# TLC5973.net
KiCad netlist of a schematic drawn in EAGLE
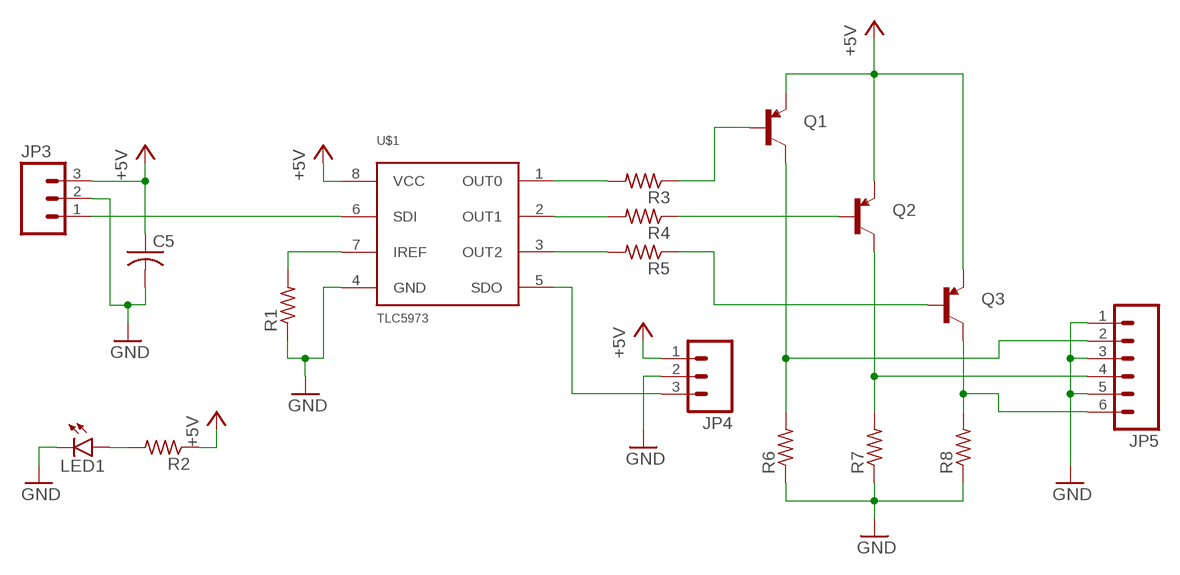
[diagram p0: schematic, sheet 1]

(export (version "E")
  (design (tool "Eeschema 10.0.6"))
  (components
    (comp (ref "C5")
      (value "C-USC0805K")
      (footprint "eagle-import:C0805K")
      (libsource (lib "eagle-import") (part "C-USC0805K"))
    )
    (comp (ref "JP3")
      (value "M03LOCK")
      (footprint "eagle-import:1X03_LOCK")
      (libsource (lib "eagle-import") (part "M03LOCK"))
    )
    (comp (ref "JP4")
      (value "M03LOCK")
      (footprint "eagle-import:1X03_LOCK")
      (libsource (lib "eagle-import") (part "M03LOCK"))
    )
    (comp (ref "JP5")
      (value "M06LOCK")
      (footprint "eagle-import:1X06_LOCK")
      (libsource (lib "eagle-import") (part "M06LOCK"))
    )
    (comp (ref "LED1")
      (value "LED1206")
      (footprint "eagle-import:LED-1206")
      (libsource (lib "eagle-import") (part "LED1206"))
    )
    (comp (ref "Q1")
      (value "TRANSISTOR_PNPSMD")
      (footprint "eagle-import:SOT23-3")
      (libsource (lib "eagle-import") (part "TRANSISTOR_PNPSMD"))
    )
    (comp (ref "Q2")
      (value "TRANSISTOR_PNPSMD")
      (footprint "eagle-import:SOT23-3")
      (libsource (lib "eagle-import") (part "TRANSISTOR_PNPSMD"))
    )
    (comp (ref "Q3")
      (value "TRANSISTOR_PNPSMD")
      (footprint "eagle-import:SOT23-3")
      (libsource (lib "eagle-import") (part "TRANSISTOR_PNPSMD"))
    )
    (comp (ref "R1")
      (value "R-US_R0805")
      (footprint "eagle-import:R0805")
      (libsource (lib "eagle-import") (part "R-US_R0805"))
    )
    (comp (ref "R2")
      (value "R-US_R0805")
      (footprint "eagle-import:R0805")
      (libsource (lib "eagle-import") (part "R-US_R0805"))
    )
    (comp (ref "R3")
      (value "R-US_R0805")
      (footprint "eagle-import:R0805")
      (libsource (lib "eagle-import") (part "R-US_R0805"))
    )
    (comp (ref "R4")
      (value "R-US_R0805")
      (footprint "eagle-import:R0805")
      (libsource (lib "eagle-import") (part "R-US_R0805"))
    )
    (comp (ref "R5")
      (value "R-US_R0805")
      (footprint "eagle-import:R0805")
      (libsource (lib "eagle-import") (part "R-US_R0805"))
    )
    (comp (ref "R6")
      (value "R-US_R0805")
      (footprint "eagle-import:R0805")
      (libsource (lib "eagle-import") (part "R-US_R0805"))
    )
    (comp (ref "R7")
      (value "R-US_R0805")
      (footprint "eagle-import:R0805")
      (libsource (lib "eagle-import") (part "R-US_R0805"))
    )
    (comp (ref "R8")
      (value "R-US_R0805")
      (footprint "eagle-import:R0805")
      (libsource (lib "eagle-import") (part "R-US_R0805"))
    )
    (comp (ref "U$1")
      (value "TLC5973")
      (footprint "eagle-import:SO-08")
      (libsource (lib "eagle-import") (part "TLC5973"))
    )
  )
  (nets
    (net (code "1") (name "+5V") (class "Default")
      (node (ref "C5") (pin "1") (pinfunction "1_1") (pintype "passive"))
      (node (ref "JP3") (pin "3") (pinfunction "3_3") (pintype "passive"))
      (node (ref "JP4") (pin "1") (pinfunction "1_1") (pintype "passive"))
      (node (ref "Q1") (pin "2") (pinfunction "E_2") (pintype "passive"))
      (node (ref "Q2") (pin "2") (pinfunction "E_2") (pintype "passive"))
      (node (ref "Q3") (pin "2") (pinfunction "E_2") (pintype "passive"))
      (node (ref "R2") (pin "1") (pinfunction "1_1") (pintype "passive"))
      (node (ref "U$1") (pin "8") (pinfunction "VCC_8") (pintype "power_in"))
    )
    (net (code "2") (name "GND") (class "Default")
      (node (ref "C5") (pin "2") (pinfunction "2_2") (pintype "passive"))
      (node (ref "JP3") (pin "2") (pinfunction "2_2") (pintype "passive"))
      (node (ref "JP4") (pin "2") (pinfunction "2_2") (pintype "passive"))
      (node (ref "JP5") (pin "1") (pinfunction "1_1") (pintype "passive"))
      (node (ref "JP5") (pin "3") (pinfunction "3_3") (pintype "passive"))
      (node (ref "JP5") (pin "5") (pinfunction "5_5") (pintype "passive"))
      (node (ref "LED1") (pin "C") (pinfunction "C_C") (pintype "passive"))
      (node (ref "R1") (pin "1") (pinfunction "1_1") (pintype "passive"))
      (node (ref "R6") (pin "1") (pinfunction "1_1") (pintype "passive"))
      (node (ref "R7") (pin "1") (pinfunction "1_1") (pintype "passive"))
      (node (ref "R8") (pin "1") (pinfunction "1_1") (pintype "passive"))
      (node (ref "U$1") (pin "4") (pinfunction "GND_4") (pintype "power_in"))
    )
    (net (code "3") (name "Net-(LED1-PadA)") (class "Default")
      (node (ref "LED1") (pin "A") (pinfunction "A_A") (pintype "passive"))
      (node (ref "R2") (pin "2") (pinfunction "2_2") (pintype "passive"))
    )
    (net (code "4") (name "Net-(Q1-B)") (class "Default")
      (node (ref "Q1") (pin "1") (pinfunction "B_1") (pintype "passive"))
      (node (ref "R3") (pin "1") (pinfunction "1_1") (pintype "passive"))
    )
    (net (code "5") (name "Net-(Q1-C)") (class "Default")
      (node (ref "JP5") (pin "2") (pinfunction "2_2") (pintype "passive"))
      (node (ref "Q1") (pin "3") (pinfunction "C_3") (pintype "passive"))
      (node (ref "R6") (pin "2") (pinfunction "2_2") (pintype "passive"))
    )
    (net (code "6") (name "Net-(Q2-B)") (class "Default")
      (node (ref "Q2") (pin "1") (pinfunction "B_1") (pintype "passive"))
      (node (ref "R4") (pin "1") (pinfunction "1_1") (pintype "passive"))
    )
    (net (code "7") (name "Net-(Q2-C)") (class "Default")
      (node (ref "JP5") (pin "4") (pinfunction "4_4") (pintype "passive"))
      (node (ref "Q2") (pin "3") (pinfunction "C_3") (pintype "passive"))
      (node (ref "R7") (pin "2") (pinfunction "2_2") (pintype "passive"))
    )
    (net (code "8") (name "Net-(Q3-B)") (class "Default")
      (node (ref "Q3") (pin "1") (pinfunction "B_1") (pintype "passive"))
      (node (ref "R5") (pin "1") (pinfunction "1_1") (pintype "passive"))
    )
    (net (code "9") (name "Net-(Q3-C)") (class "Default")
      (node (ref "JP5") (pin "6") (pinfunction "6_6") (pintype "passive"))
      (node (ref "Q3") (pin "3") (pinfunction "C_3") (pintype "passive"))
      (node (ref "R8") (pin "2") (pinfunction "2_2") (pintype "passive"))
    )
    (net (code "10") (name "Net-(U$1-IREF)") (class "Default")
      (node (ref "R1") (pin "2") (pinfunction "2_2") (pintype "passive"))
      (node (ref "U$1") (pin "7") (pinfunction "IREF_7") (pintype "bidirectional"))
    )
    (net (code "11") (name "Net-(U$1-OUT0)") (class "Default")
      (node (ref "R3") (pin "2") (pinfunction "2_2") (pintype "passive"))
      (node (ref "U$1") (pin "1") (pinfunction "OUT0_1") (pintype "output"))
    )
    (net (code "12") (name "Net-(U$1-OUT1)") (class "Default")
      (node (ref "R4") (pin "2") (pinfunction "2_2") (pintype "passive"))
      (node (ref "U$1") (pin "2") (pinfunction "OUT1_2") (pintype "output"))
    )
    (net (code "13") (name "Net-(U$1-OUT2)") (class "Default")
      (node (ref "R5") (pin "2") (pinfunction "2_2") (pintype "passive"))
      (node (ref "U$1") (pin "3") (pinfunction "OUT2_3") (pintype "output"))
    )
    (net (code "14") (name "Net-(U$1-SDI)") (class "Default")
      (node (ref "JP3") (pin "1") (pinfunction "1_1") (pintype "passive"))
      (node (ref "U$1") (pin "6") (pinfunction "SDI_6") (pintype "input"))
    )
    (net (code "15") (name "Net-(U$1-SDO)") (class "Default")
      (node (ref "JP4") (pin "3") (pinfunction "3_3") (pintype "passive"))
      (node (ref "U$1") (pin "5") (pinfunction "SDO_5") (pintype "output"))
    )
  )
)
